# Temp.net
KiCad netlist of a schematic drawn in EAGLE
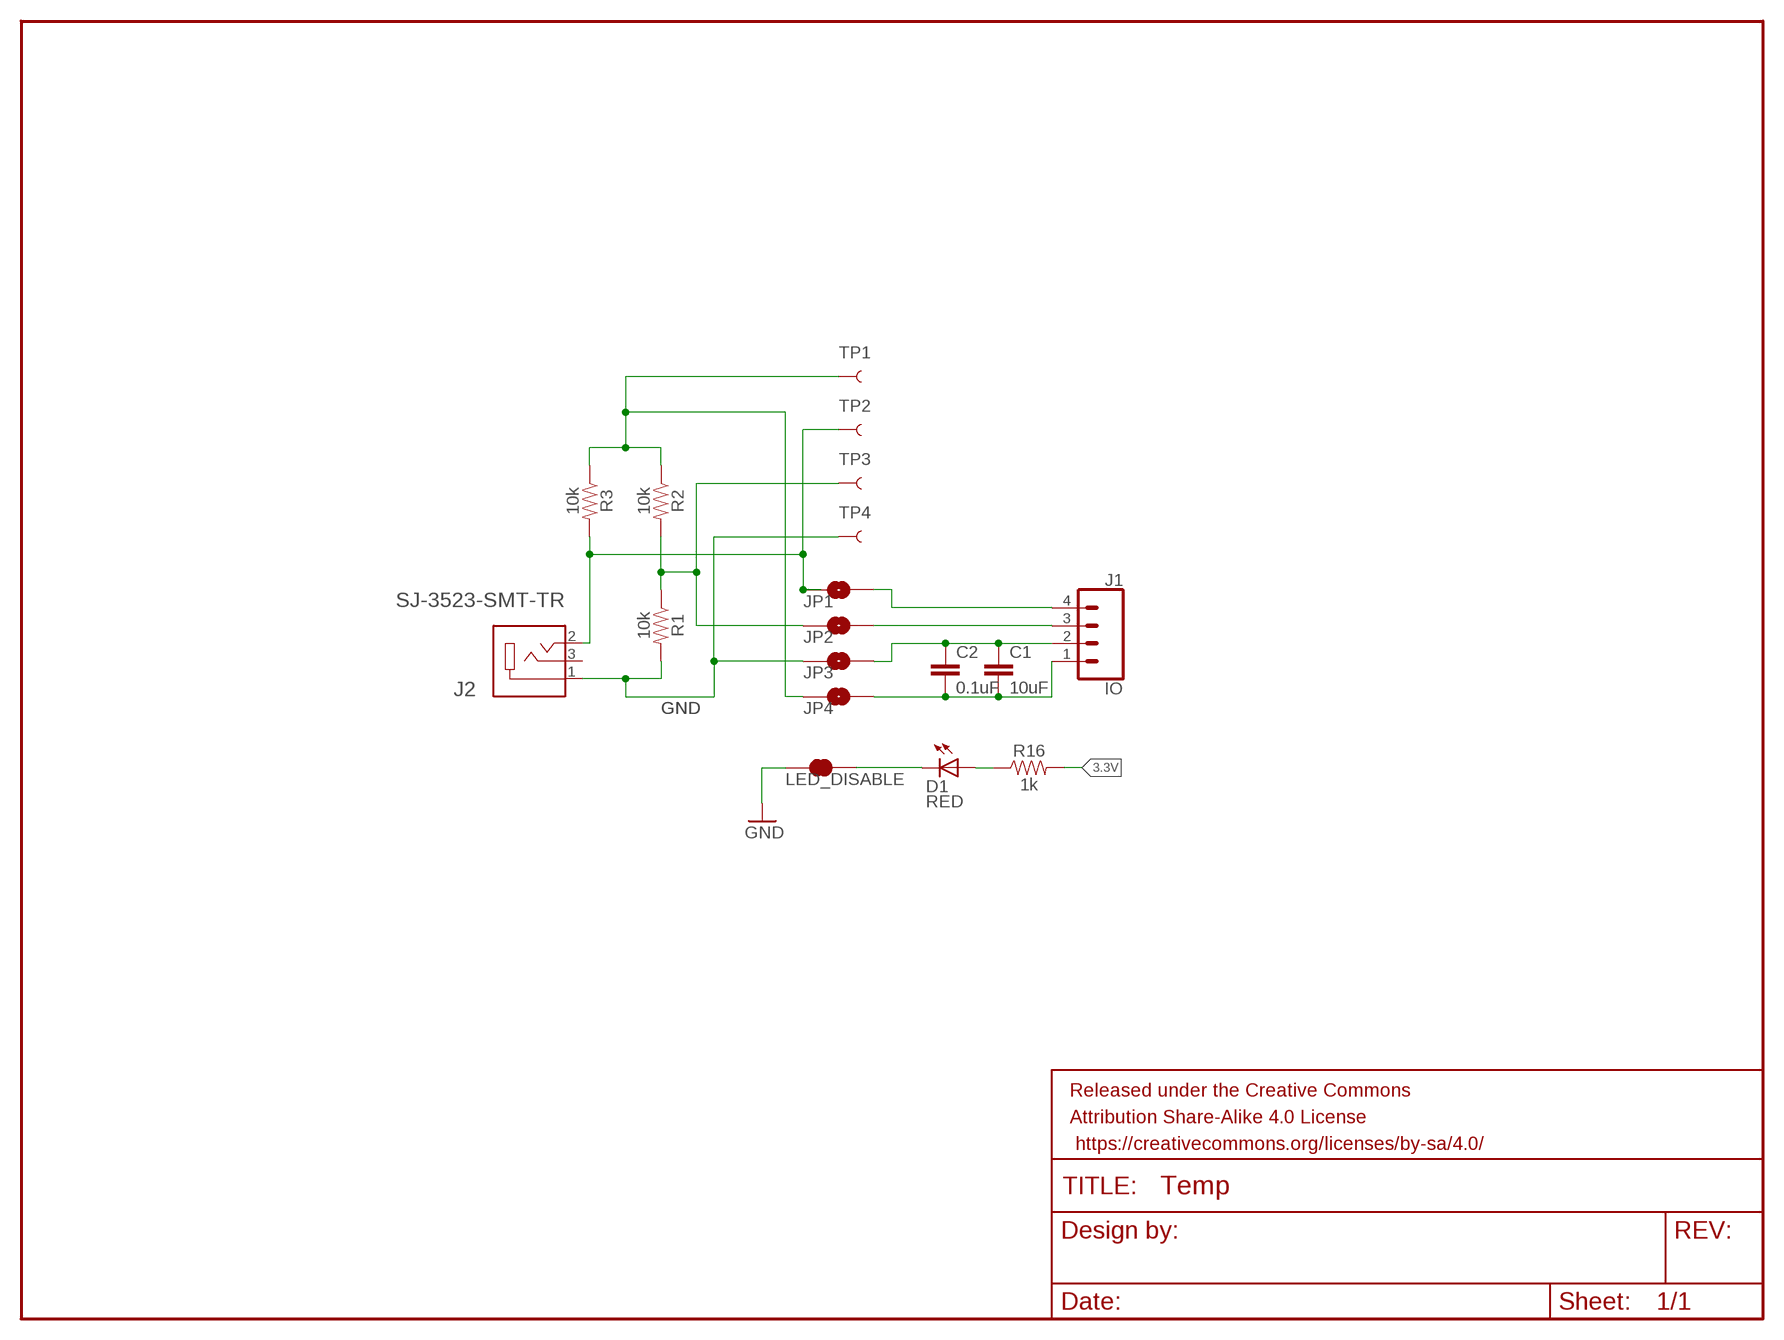
[diagram p0: schematic, sheet 1]

(export (version "E")
  (design (tool "Eeschema 10.0.6"))
  (components
    (comp (ref "C1")
      (value "10uF")
      (footprint "eagle-import:0603")
      (libsource (lib "eagle-import") (part "10UF-0603-6.3V-20%"))
    )
    (comp (ref "C2")
      (value "0.1uF")
      (footprint "eagle-import:0603")
      (libsource (lib "eagle-import") (part "0.1UF-0603-25V-(+80/-20%)"))
    )
    (comp (ref "D1")
      (value "RED")
      (footprint "eagle-import:LED-0603")
      (libsource (lib "eagle-import") (part "LED-RED0603"))
    )
    (comp (ref "FRAME1")
      (value "FRAME-LETTERNO_PACKAGE")
      (footprint "eagle-import:DUMMY")
      (fields (field (name "DESIGNER") "Nobody"))
      (libsource (lib "eagle-import") (part "FRAME-LETTERNO_PACKAGE"))
    )
    (comp (ref "J1")
      (value "IO")
      (footprint "eagle-import:1X04")
      (libsource (lib "eagle-import") (part "CONN_04"))
    )
    (comp (ref "J2")
      (value "SJ-3523-SMT-TR")
      (footprint "eagle-import:CUI_SJ-3523-SMT-TR")
      (fields (field (name "MF") "CUI Devices"))
      (libsource (lib "eagle-import") (part "SJ-3523-SMT-TR"))
    )
    (comp (ref "JP1")
      (value "JUMPER-SMT_2_NO_NO-SILK")
      (footprint "eagle-import:SMT-JUMPER_2_NO_NO-SILK")
      (libsource (lib "eagle-import") (part "JUMPER-SMT_2_NO_NO-SILK"))
    )
    (comp (ref "JP2")
      (value "JUMPER-SMT_2_NO_NO-SILK")
      (footprint "eagle-import:SMT-JUMPER_2_NO_NO-SILK")
      (libsource (lib "eagle-import") (part "JUMPER-SMT_2_NO_NO-SILK"))
    )
    (comp (ref "JP3")
      (value "JUMPER-SMT_2_NO_NO-SILK")
      (footprint "eagle-import:SMT-JUMPER_2_NO_NO-SILK")
      (libsource (lib "eagle-import") (part "JUMPER-SMT_2_NO_NO-SILK"))
    )
    (comp (ref "JP4")
      (value "JUMPER-SMT_2_NO_NO-SILK")
      (footprint "eagle-import:SMT-JUMPER_2_NO_NO-SILK")
      (libsource (lib "eagle-import") (part "JUMPER-SMT_2_NO_NO-SILK"))
    )
    (comp (ref "LED_DISABLE")
      (value "JUMPER-SMT_2_NC_TRACE_SILK")
      (footprint "eagle-import:SMT-JUMPER_2_NC_TRACE_SILK")
      (libsource (lib "eagle-import") (part "JUMPER-SMT_2_NC_TRACE_SILK"))
    )
    (comp (ref "R1")
      (value "10k")
      (footprint "eagle-import:0603")
      (libsource (lib "eagle-import") (part "10KOHM-0603-1/10W-1%"))
    )
    (comp (ref "R2")
      (value "10k")
      (footprint "eagle-import:0603")
      (libsource (lib "eagle-import") (part "10KOHM-0603-1/10W-1%"))
    )
    (comp (ref "R3")
      (value "10k")
      (footprint "eagle-import:0603")
      (libsource (lib "eagle-import") (part "10KOHM-0603-1/10W-1%"))
    )
    (comp (ref "R16")
      (value "1k")
      (footprint "eagle-import:0603")
      (libsource (lib "eagle-import") (part "1KOHM-0603-1/10W-1%"))
    )
    (comp (ref "TP1")
      (value "TEST-POINT3X5")
      (footprint "eagle-import:PAD.03X.05")
      (libsource (lib "eagle-import") (part "TEST-POINT3X5"))
    )
    (comp (ref "TP2")
      (value "TEST-POINT3X5")
      (footprint "eagle-import:PAD.03X.05")
      (libsource (lib "eagle-import") (part "TEST-POINT3X5"))
    )
    (comp (ref "TP3")
      (value "TEST-POINT3X5")
      (footprint "eagle-import:PAD.03X.05")
      (libsource (lib "eagle-import") (part "TEST-POINT3X5"))
    )
    (comp (ref "TP4")
      (value "TEST-POINT3X5")
      (footprint "eagle-import:PAD.03X.05")
      (libsource (lib "eagle-import") (part "TEST-POINT3X5"))
    )
  )
  (nets
    (net (code "1") (name "3.3V") (class "Default")
      (node (ref "JP4") (pin "1") (pinfunction "1_1") (pintype "passive"))
      (node (ref "R16") (pin "2") (pinfunction "2_2") (pintype "passive"))
      (node (ref "R2") (pin "1") (pinfunction "1_1") (pintype "passive"))
      (node (ref "R3") (pin "1") (pinfunction "1_1") (pintype "passive"))
      (node (ref "TP1") (pin "P$1") (pinfunction "1_P$1") (pintype "bidirectional"))
    )
    (net (code "2") (name "GND") (class "Default")
      (node (ref "J2") (pin "1") (pinfunction "1_1") (pintype "passive"))
      (node (ref "JP3") (pin "1") (pinfunction "1_1") (pintype "passive"))
      (node (ref "LED_DISABLE") (pin "1") (pinfunction "1_1") (pintype "passive"))
      (node (ref "R1") (pin "2") (pinfunction "2_2") (pintype "passive"))
      (node (ref "TP4") (pin "P$1") (pinfunction "1_P$1") (pintype "bidirectional"))
    )
    (net (code "3") (name "Net-(C1-Pad1)") (class "Default")
      (node (ref "C1") (pin "1") (pinfunction "1_1") (pintype "passive"))
      (node (ref "C2") (pin "1") (pinfunction "1_1") (pintype "passive"))
      (node (ref "J1") (pin "2") (pinfunction "2_2") (pintype "passive"))
      (node (ref "JP3") (pin "2") (pinfunction "2_2") (pintype "passive"))
    )
    (net (code "4") (name "Net-(C1-Pad2)") (class "Default")
      (node (ref "C1") (pin "2") (pinfunction "2_2") (pintype "passive"))
      (node (ref "C2") (pin "2") (pinfunction "2_2") (pintype "passive"))
      (node (ref "J1") (pin "1") (pinfunction "1_1") (pintype "passive"))
      (node (ref "JP4") (pin "2") (pinfunction "2_2") (pintype "passive"))
    )
    (net (code "5") (name "Net-(D1-PadA)") (class "Default")
      (node (ref "D1") (pin "A") (pinfunction "A_A") (pintype "passive"))
      (node (ref "R16") (pin "1") (pinfunction "1_1") (pintype "passive"))
    )
    (net (code "6") (name "Net-(D1-PadC)") (class "Default")
      (node (ref "D1") (pin "C") (pinfunction "C_C") (pintype "passive"))
      (node (ref "LED_DISABLE") (pin "2") (pinfunction "2_2") (pintype "passive"))
    )
    (net (code "7") (name "Net-(J1-Pad3)") (class "Default")
      (node (ref "J1") (pin "3") (pinfunction "3_3") (pintype "passive"))
      (node (ref "JP2") (pin "2") (pinfunction "2_2") (pintype "passive"))
    )
    (net (code "8") (name "Net-(J1-Pad4)") (class "Default")
      (node (ref "J1") (pin "4") (pinfunction "4_4") (pintype "passive"))
      (node (ref "JP1") (pin "2") (pinfunction "2_2") (pintype "passive"))
    )
    (net (code "9") (name "Net-(TP2-1)") (class "Default")
      (node (ref "J2") (pin "2") (pinfunction "2_2") (pintype "passive"))
      (node (ref "JP1") (pin "1") (pinfunction "1_1") (pintype "passive"))
      (node (ref "R3") (pin "2") (pinfunction "2_2") (pintype "passive"))
      (node (ref "TP2") (pin "P$1") (pinfunction "1_P$1") (pintype "bidirectional"))
    )
    (net (code "10") (name "Net-(TP3-1)") (class "Default")
      (node (ref "JP2") (pin "1") (pinfunction "1_1") (pintype "passive"))
      (node (ref "R1") (pin "1") (pinfunction "1_1") (pintype "passive"))
      (node (ref "R2") (pin "2") (pinfunction "2_2") (pintype "passive"))
      (node (ref "TP3") (pin "P$1") (pinfunction "1_P$1") (pintype "bidirectional"))
    )
    (net (code "11") (name "unconnected-(J2-Pad3)") (class "Default")
      (node (ref "J2") (pin "3") (pinfunction "3_3") (pintype "passive"))
    )
  )
)
